# MCU_Data_collector.net
KiCad netlist of a schematic drawn in Altium Designer
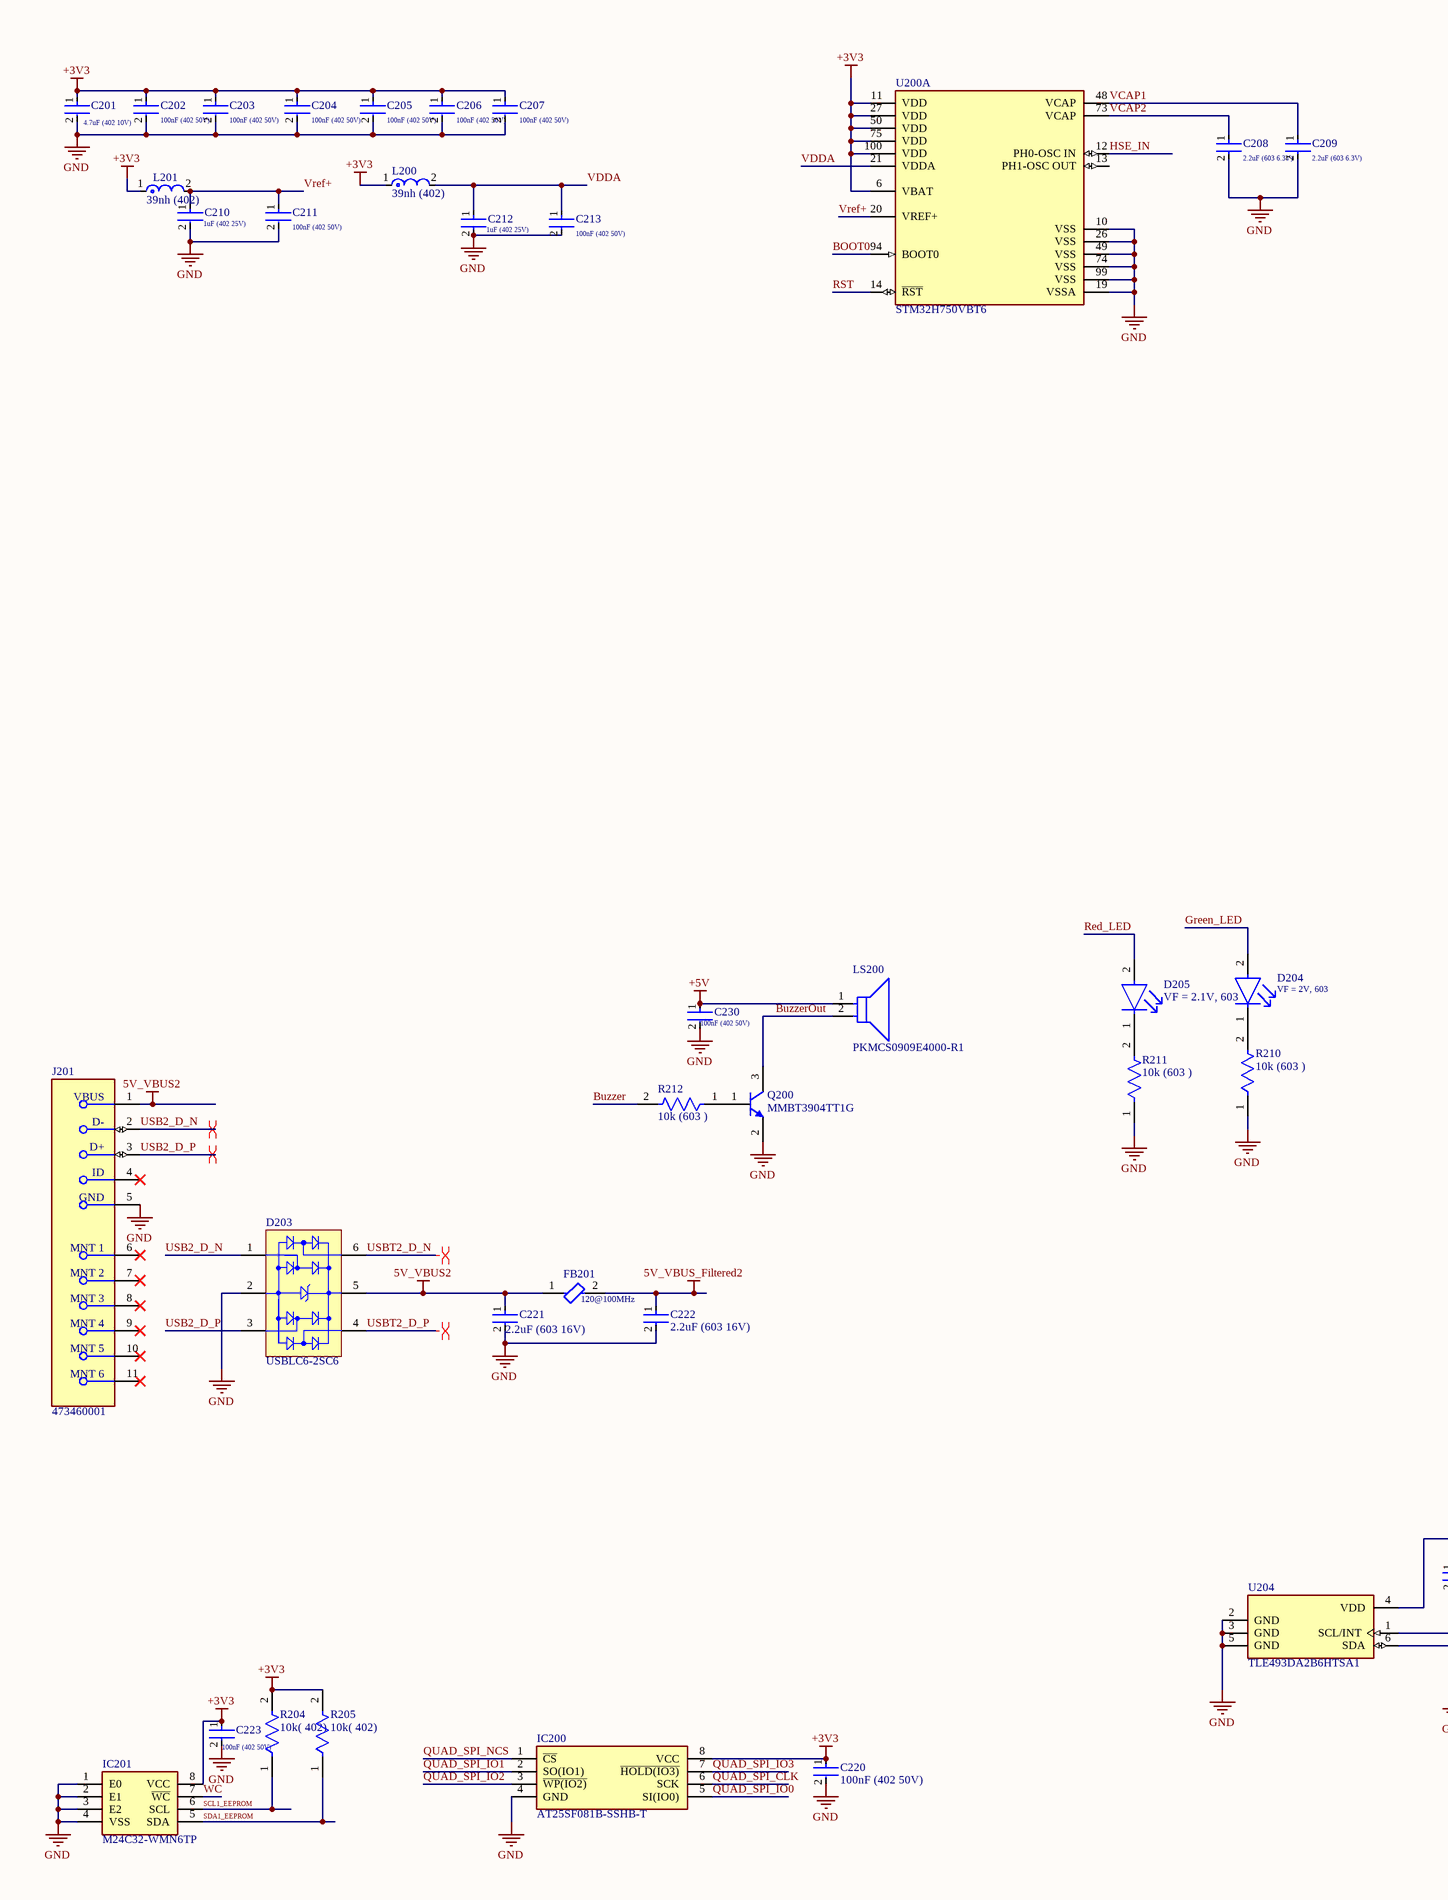
[diagram p0: MCU_Data_collector.SchDoc, left]
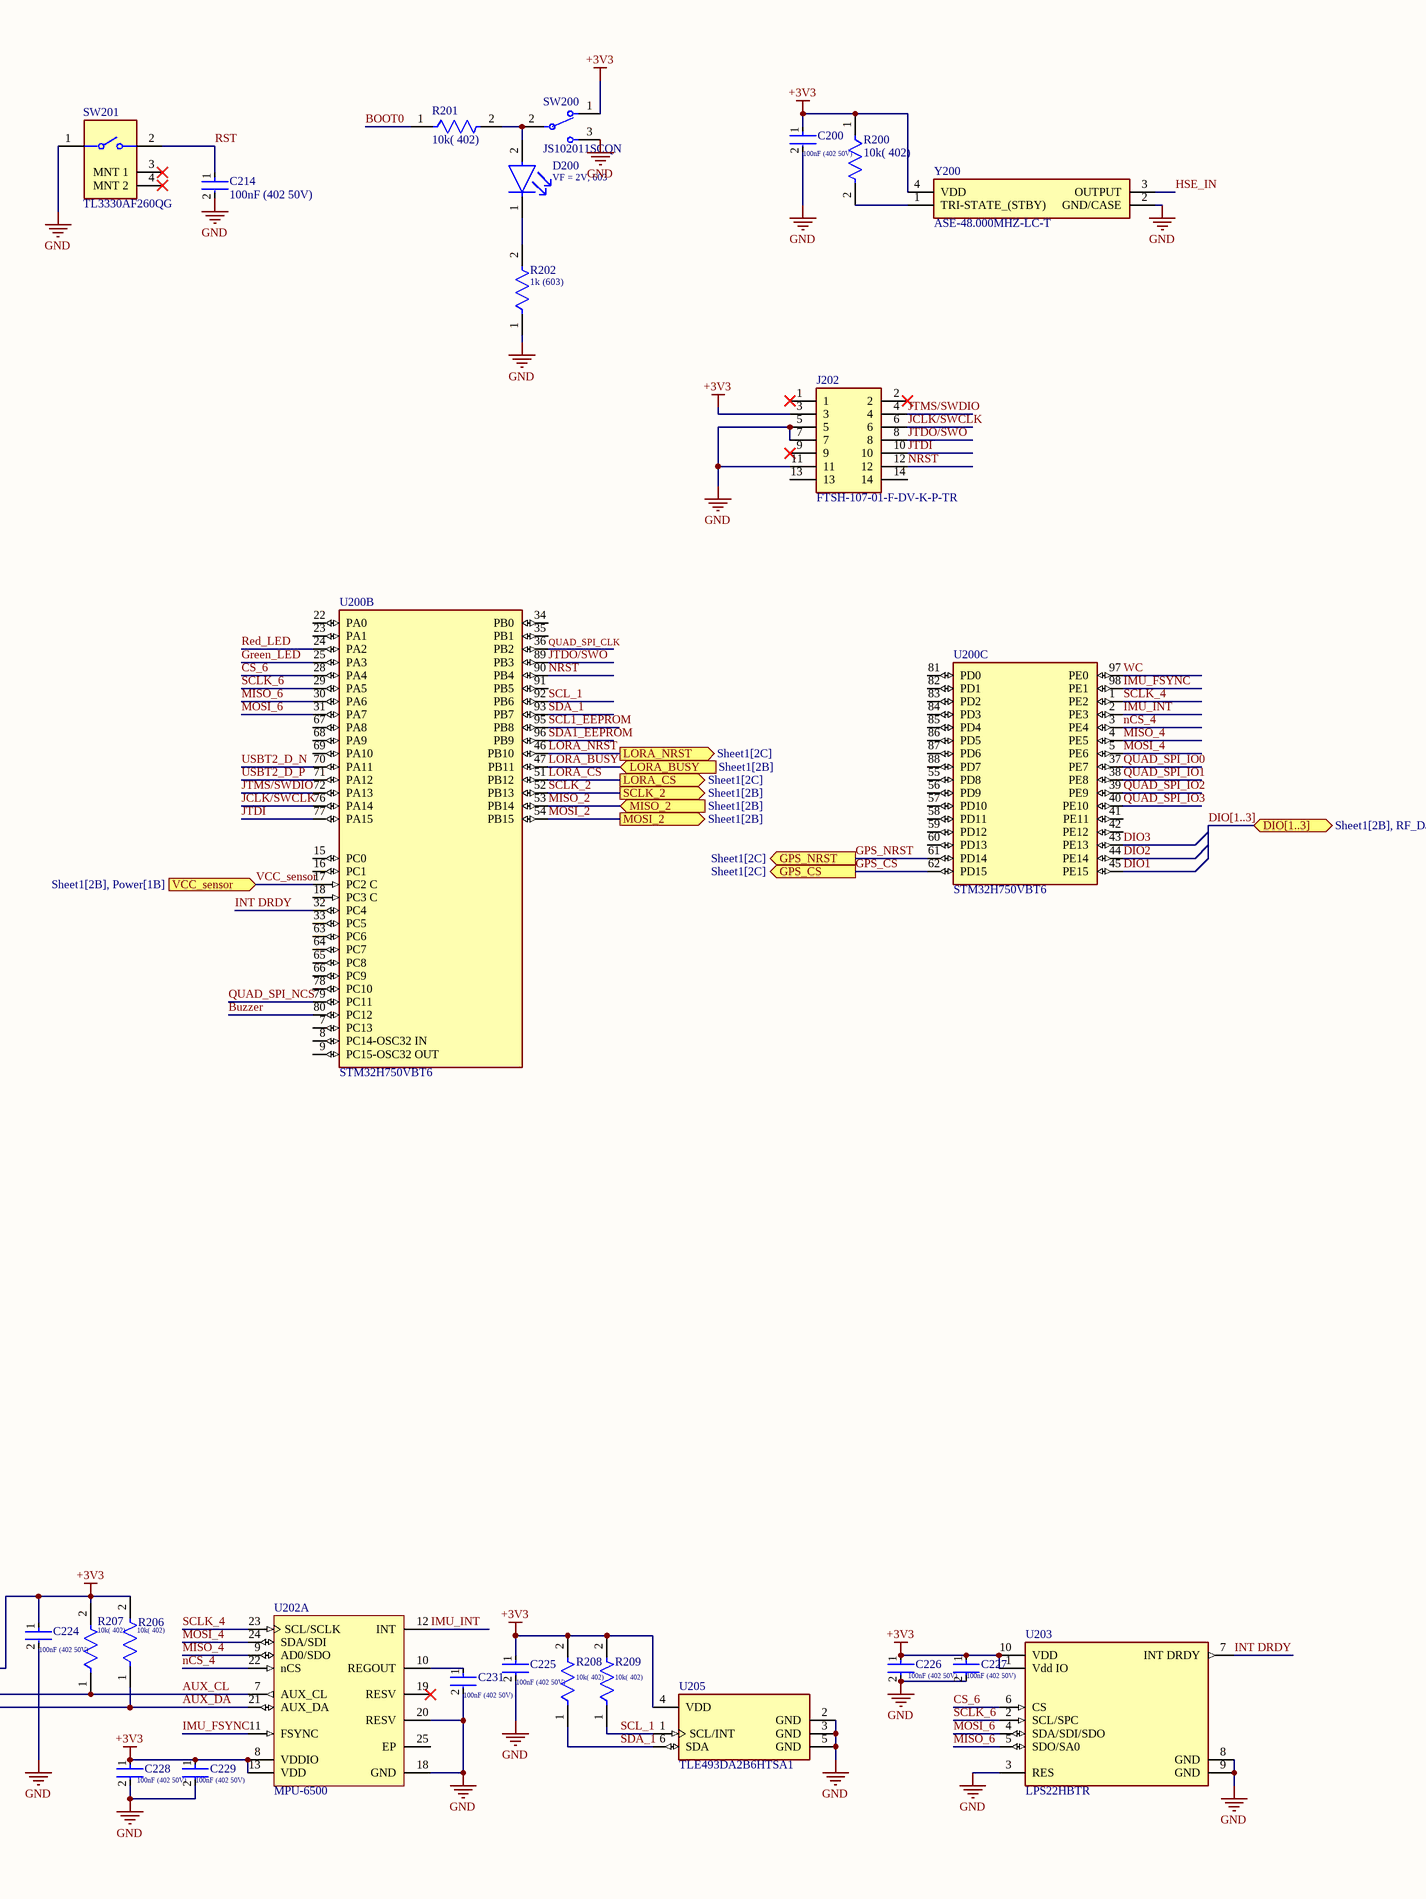
[diagram p1: MCU_Data_collector.SchDoc, right]

(export (version "E")
  (design (tool "Eeschema 10.0.6"))
  (components
    (comp (ref "C200")
      (value "100nF (402 50V)")
      (footprint "FP-CL779-IPC_C")
      (description "Cap Ceramic 100nF 50V X7R ±10% SMD 0402 +125°C Paper T/R")
      (libsource (lib "Altium Content Vault") (part "b4654b650e69147ec39a6b967a45e02"))
    )
    (comp (ref "C201")
      (value "4.7uF (402 10V)")
      (footprint "FP-CL282-IPC_C")
      (description "Cap Ceramic 4.7uF 10V X5R ±20% SMD 0402 +85°C Paper T/R")
      (fields (field (name "TOLERANCE") "20%"))
      (libsource (lib "Altium Content Vault") (part "b4654b650e69147ec39a6b967a45e02"))
    )
    (comp (ref "C202")
      (value "100nF (402 50V)")
      (footprint "FP-CL779-IPC_C")
      (description "Cap Ceramic 100nF 50V X7R ±10% SMD 0402 +125°C Paper T/R")
      (libsource (lib "Altium Content Vault") (part "b4654b650e69147ec39a6b967a45e02"))
    )
    (comp (ref "C203")
      (value "100nF (402 50V)")
      (footprint "FP-CL779-IPC_C")
      (description "Cap Ceramic 100nF 50V X7R ±10% SMD 0402 +125°C Paper T/R")
      (libsource (lib "Altium Content Vault") (part "b4654b650e69147ec39a6b967a45e02"))
    )
    (comp (ref "C204")
      (value "100nF (402 50V)")
      (footprint "FP-CL779-IPC_C")
      (description "Cap Ceramic 100nF 50V X7R ±10% SMD 0402 +125°C Paper T/R")
      (libsource (lib "Altium Content Vault") (part "b4654b650e69147ec39a6b967a45e02"))
    )
    (comp (ref "C205")
      (value "100nF (402 50V)")
      (footprint "FP-CL779-IPC_C")
      (description "Cap Ceramic 100nF 50V X7R ±10% SMD 0402 +125°C Paper T/R")
      (libsource (lib "Altium Content Vault") (part "b4654b650e69147ec39a6b967a45e02"))
    )
    (comp (ref "C206")
      (value "100nF (402 50V)")
      (footprint "FP-CL779-IPC_C")
      (description "Cap Ceramic 100nF 50V X7R ±10% SMD 0402 +125°C Paper T/R")
      (libsource (lib "Altium Content Vault") (part "b4654b650e69147ec39a6b967a45e02"))
    )
    (comp (ref "C207")
      (value "100nF (402 50V)")
      (footprint "FP-CL779-IPC_C")
      (description "Cap Ceramic 100nF 50V X7R ±10% SMD 0402 +125°C Paper T/R")
      (libsource (lib "Altium Content Vault") (part "b4654b650e69147ec39a6b967a45e02"))
    )
    (comp (ref "C208")
      (value "2.2uF (603 6.3V)")
      (footprint "FP-CL50-IPC_C")
      (description "Cap Ceramic 2.2uF 6.3V X5R ±20% SMD 0402 +85°C Paper T/R")
      (fields (field (name "TOLERANCE") "20%"))
      (libsource (lib "Altium Content Vault") (part "b4654b650e69147ec39a6b967a45e02"))
    )
    (comp (ref "C209")
      (value "2.2uF (603 6.3V)")
      (footprint "FP-CL50-IPC_C")
      (description "Cap Ceramic 2.2uF 6.3V X5R ±20% SMD 0402 +85°C Paper T/R")
      (fields (field (name "TOLERANCE") "20%"))
      (libsource (lib "Altium Content Vault") (part "b4654b650e69147ec39a6b967a45e02"))
    )
    (comp (ref "C210")
      (value "1uF (402 25V)")
      (footprint "FP-CL542-IPC_C")
      (description "Cap Ceramic 1uF 25V X5R ±10% SMD 0402 +85°C Paper T/R")
      (fields (field (name "TOLERANCE") "10%"))
      (libsource (lib "Altium Content Vault") (part "b4654b650e69147ec39a6b967a45e02"))
    )
    (comp (ref "C211")
      (value "100nF (402 50V)")
      (footprint "FP-CL779-IPC_C")
      (description "Cap Ceramic 100nF 50V X7R ±10% SMD 0402 +125°C Paper T/R")
      (libsource (lib "Altium Content Vault") (part "b4654b650e69147ec39a6b967a45e02"))
    )
    (comp (ref "C212")
      (value "1uF (402 25V)")
      (footprint "FP-CL542-IPC_C")
      (description "Cap Ceramic 1uF 25V X5R ±10% SMD 0402 +85°C Paper T/R")
      (fields (field (name "TOLERANCE") "10%"))
      (libsource (lib "Altium Content Vault") (part "b4654b650e69147ec39a6b967a45e02"))
    )
    (comp (ref "C213")
      (value "100nF (402 50V)")
      (footprint "FP-CL779-IPC_C")
      (description "Cap Ceramic 100nF 50V X7R ±10% SMD 0402 +125°C Paper T/R")
      (libsource (lib "Altium Content Vault") (part "b4654b650e69147ec39a6b967a45e02"))
    )
    (comp (ref "C214")
      (value "100nF (402 50V)")
      (footprint "FP-CL779-IPC_C")
      (description "Cap Ceramic 100nF 50V X7R ±10% SMD 0402 +125°C Paper T/R")
      (libsource (lib "Altium Content Vault") (part "b4654b650e69147ec39a6b967a45e02"))
    )
    (comp (ref "C220")
      (value "100nF (402 50V)")
      (footprint "FP-CL779-IPC_C")
      (description "Cap Ceramic 100nF 50V X7R ±10% SMD 0402 +125°C Paper T/R")
      (libsource (lib "Altium Content Vault") (part "b4654b650e69147ec39a6b967a45e02"))
    )
    (comp (ref "C221")
      (value "2.2uF (603 16V)")
      (footprint "FP-CL10-IPC_A")
      (description "Cap Ceramic 2.2uF 16V X5R ±10% Pad SMD 0603 +85°C T/R")
      (fields (field (name "TOLERANCE") "10%") (field (name "VOLTAGE") "16V"))
      (libsource (lib "Altium Content Vault") (part "b4654b650e69147ec39a6b967a45e02"))
    )
    (comp (ref "C222")
      (value "2.2uF (603 16V)")
      (footprint "FP-CL10-IPC_A")
      (description "Cap Ceramic 2.2uF 16V X5R ±10% Pad SMD 0603 +85°C T/R")
      (fields (field (name "TOLERANCE") "10%") (field (name "VOLTAGE") "16V"))
      (libsource (lib "Altium Content Vault") (part "b4654b650e69147ec39a6b967a45e02"))
    )
    (comp (ref "C223")
      (value "100nF (402 50V)")
      (footprint "FP-CL779-IPC_C")
      (description "Cap Ceramic 100nF 50V X7R ±10% SMD 0402 +125°C Paper T/R")
      (libsource (lib "Altium Content Vault") (part "b4654b650e69147ec39a6b967a45e02"))
    )
    (comp (ref "C224")
      (value "100nF (402 50V)")
      (footprint "FP-CL779-IPC_C")
      (description "Cap Ceramic 100nF 50V X7R ±10% SMD 0402 +125°C Paper T/R")
      (libsource (lib "Altium Content Vault") (part "b4654b650e69147ec39a6b967a45e02"))
    )
    (comp (ref "C225")
      (value "100nF (402 50V)")
      (footprint "FP-CL779-IPC_C")
      (description "Cap Ceramic 100nF 50V X7R ±10% SMD 0402 +125°C Paper T/R")
      (libsource (lib "Altium Content Vault") (part "b4654b650e69147ec39a6b967a45e02"))
    )
    (comp (ref "C226")
      (value "100nF (402 50V)")
      (footprint "FP-CL779-IPC_C")
      (description "Cap Ceramic 100nF 50V X7R ±10% SMD 0402 +125°C Paper T/R")
      (libsource (lib "Altium Content Vault") (part "b4654b650e69147ec39a6b967a45e02"))
    )
    (comp (ref "C227")
      (value "100nF (402 50V)")
      (footprint "FP-CL779-IPC_C")
      (description "Cap Ceramic 100nF 50V X7R ±10% SMD 0402 +125°C Paper T/R")
      (libsource (lib "Altium Content Vault") (part "b4654b650e69147ec39a6b967a45e02"))
    )
    (comp (ref "C228")
      (value "100nF (402 50V)")
      (footprint "FP-CL779-IPC_C")
      (description "Cap Ceramic 100nF 50V X7R ±10% SMD 0402 +125°C Paper T/R")
      (libsource (lib "Altium Content Vault") (part "b4654b650e69147ec39a6b967a45e02"))
    )
    (comp (ref "C229")
      (value "100nF (402 50V)")
      (footprint "FP-CL779-IPC_C")
      (description "Cap Ceramic 100nF 50V X7R ±10% SMD 0402 +125°C Paper T/R")
      (libsource (lib "Altium Content Vault") (part "b4654b650e69147ec39a6b967a45e02"))
    )
    (comp (ref "C230")
      (value "100nF (402 50V)")
      (footprint "FP-CL779-IPC_C")
      (description "Cap Ceramic 100nF 50V X7R ±10% SMD 0402 +125°C Paper T/R")
      (libsource (lib "Altium Content Vault") (part "b4654b650e69147ec39a6b967a45e02"))
    )
    (comp (ref "C231")
      (value "100nF (402 50V)")
      (footprint "FP-CL779-IPC_C")
      (description "Cap Ceramic 100nF 50V X7R ±10% SMD 0402 +125°C Paper T/R")
      (libsource (lib "Altium Content Vault") (part "b4654b650e69147ec39a6b967a45e02"))
    )
    (comp (ref "D200")
      (value "VF = 2V, 603")
      (footprint "FP-LTST-C191KGKT-MFG")
      (description "LED GREEN CLEAR SMD")
      (libsource (lib "Altium Content Vault") (part "8706943c75ba83719d021d2fdc84c58"))
    )
    (comp (ref "D203")
      (value "USBLC6-2SC6")
      (footprint "STM-SOT23-6L_V")
      (description "Very low capacitance ESD protection, 3.5 pF, -40 to 125 degC, 6-Pin SOT23, RoHS, Tape and Reel")
      (fields (field (name "MANUFACTURER") "STMicroelectronics"))
      (libsource (lib "Altium Content Vault") (part "STM-USB_DVI_HDMIULC6-4SC6X-SOT23-6L"))
    )
    (comp (ref "D204")
      (value "VF = 2V, 603")
      (footprint "FP-LTST-C191KGKT-MFG")
      (description "LED GREEN CLEAR SMD")
      (libsource (lib "Altium Content Vault") (part "8706943c75ba83719d021d2fdc84c58"))
    )
    (comp (ref "D205")
      (value "VF = 2.1V, 603")
      (footprint "FP-LTST-C190KRKT-MFG")
      (description "LED RED CLEAR CHIP SMD")
      (libsource (lib "Altium Content Vault") (part "8706943c75ba83719d021d2fdc84c58"))
    )
    (comp (ref "FB201")
      (value "120@100MHz")
      (footprint "FP-BLM18-0_15-t0_8-MFG")
      (description "Chip Ferrite Bead, 0603, 120Ω @ 100MHz, 0.25Ω, 25%, 200mA")
      (fields (field (name "TOLERANCE") "25%"))
      (libsource (lib "Altium Content Vault") (part "5f30dd21d616792df468990f7003faa"))
    )
    (comp (ref "IC200")
      (value "AT25SF081B-SSHB-T")
      (footprint "SamacSys:SOIC127P600X175-8N")
      (description "Integrated Circuit")
      (fields (field (name "MOUSER PART NUMBER") "724-AT25SF081BSSHBT"))
      (libsource (lib "*") (part "AT25SF081B-SSHB-T"))
    )
    (comp (ref "IC201")
      (value "M24C32-WMN6TP")
      (footprint "SamacSys:SOIC127P600X175-8N")
      (description "Integrated Circuit")
      (fields (field (name "MOUSER PART NUMBER") "511-M24C32-WMN6TP"))
      (libsource (lib "*") (part "M24C32-WMN6TP"))
    )
    (comp (ref "J201")
      (value "473460001")
      (footprint "FP-473460001-MFG")
      (description "CONN RCPT USB2.0 MICRO B SMD R/A")
      (fields
        (field (name "OCTOPART") "https://octopart.com/47346-0001-molex-7164928")
        (field (name "MANUFACTURER") "Molex")
      )
      (libsource (lib "Altium Content Vault") (part "53ae1f1d9b557310b43ca686e5bb76a"))
    )
    (comp (ref "J202")
      (value "FTSH-107-01-F-DV-K-P-TR")
      (footprint "SamacSys:FTSH-107-XX-YYY-DV-K-P-TR")
      (description "Connector")
      (fields (field (name "MOUSER PART NUMBER") "200-FTSH10701FDVKPTR"))
      (libsource (lib "*") (part "FTSH-107-01-F-DV-K-P-TR"))
    )
    (comp (ref "L200")
      (value "39nh (402)")
      (footprint "FP-LQG15HH_02-MFG")
      (description "Multilayer type RF Inductor 39nH ±5% 1.06Ω 250mA 0402")
      (fields (field (name "TOLERANCE") "5%"))
      (libsource (lib "Altium Content Vault") (part "4cc4b267dca4c8e51f7102f422741d8"))
    )
    (comp (ref "L201")
      (value "39nh (402)")
      (footprint "FP-LQG15HH_02-MFG")
      (description "Multilayer type RF Inductor 39nH ±5% 1.06Ω 250mA 0402")
      (fields (field (name "TOLERANCE") "5%"))
      (libsource (lib "Altium Content Vault") (part "4cc4b267dca4c8e51f7102f422741d8"))
    )
    (comp (ref "LS200")
      (value "PKMCS0909E4000-R1")
      (footprint "FP-PKMCS-MFG")
      (description "AUDIO PIEZO TRANSDUCER 12.5V SMD")
      (libsource (lib "Altium Content Vault") (part "1973c4b650225fd2ddacaff6b763965"))
    )
    (comp (ref "Q200")
      (value "MMBT3904TT1G")
      (footprint "ONSC-SC-75-3-463-01_V")
      (description "General Purpose Transistor, NPN Silicon, 3-Pin SC-75, Pb-Free, Tape and Reel")
      (fields (field (name "MANUFACTURER") "On Semiconductor"))
      (libsource (lib "Altium Content Vault") (part "ONSC-NPN-B1E2C3-3"))
    )
    (comp (ref "R200")
      (value "10k( 402)")
      (footprint "FP-RC0402-0_4-IPC_C")
      (description "RES 10K OHM 5% 1/16W 0402")
      (fields (field (name "TOLERANCE") "5%"))
      (libsource (lib "Altium Content Vault") (part "1029c3af85768c4190bb7ad29bc67b5"))
    )
    (comp (ref "R201")
      (value "10k( 402)")
      (footprint "FP-RC0402-0_4-IPC_C")
      (description "RES 10K OHM 5% 1/16W 0402")
      (fields (field (name "TOLERANCE") "5%"))
      (libsource (lib "Altium Content Vault") (part "1029c3af85768c4190bb7ad29bc67b5"))
    )
    (comp (ref "R202")
      (value "1k (603)")
      (footprint "FP-CRCW0603-e3-MFG")
      (description "RES Thick Film, 1kΩ, 1%, 0.1W, 100ppm/°C, 0603")
      (fields (field (name "TOLERANCE") "1%"))
      (libsource (lib "Altium Content Vault") (part "1029c3af85768c4190bb7ad29bc67b5"))
    )
    (comp (ref "R204")
      (value "10k( 402)")
      (footprint "FP-RC0402-0_4-IPC_C")
      (description "RES 10K OHM 5% 1/16W 0402")
      (fields (field (name "TOLERANCE") "5%"))
      (libsource (lib "Altium Content Vault") (part "1029c3af85768c4190bb7ad29bc67b5"))
    )
    (comp (ref "R205")
      (value "10k( 402)")
      (footprint "FP-RC0402-0_4-IPC_C")
      (description "RES 10K OHM 5% 1/16W 0402")
      (fields (field (name "TOLERANCE") "5%"))
      (libsource (lib "Altium Content Vault") (part "1029c3af85768c4190bb7ad29bc67b5"))
    )
    (comp (ref "R206")
      (value "10k( 402)")
      (footprint "FP-RC0402-0_4-IPC_C")
      (description "RES 10K OHM 5% 1/16W 0402")
      (fields (field (name "TOLERANCE") "5%"))
      (libsource (lib "Altium Content Vault") (part "1029c3af85768c4190bb7ad29bc67b5"))
    )
    (comp (ref "R207")
      (value "10k( 402)")
      (footprint "FP-RC0402-0_4-IPC_C")
      (description "RES 10K OHM 5% 1/16W 0402")
      (fields (field (name "TOLERANCE") "5%"))
      (libsource (lib "Altium Content Vault") (part "1029c3af85768c4190bb7ad29bc67b5"))
    )
    (comp (ref "R208")
      (value "10k( 402)")
      (footprint "FP-RC0402-0_4-IPC_C")
      (description "RES 10K OHM 5% 1/16W 0402")
      (fields (field (name "TOLERANCE") "5%"))
      (libsource (lib "Altium Content Vault") (part "1029c3af85768c4190bb7ad29bc67b5"))
    )
    (comp (ref "R209")
      (value "10k( 402)")
      (footprint "FP-RC0402-0_4-IPC_C")
      (description "RES 10K OHM 5% 1/16W 0402")
      (fields (field (name "TOLERANCE") "5%"))
      (libsource (lib "Altium Content Vault") (part "1029c3af85768c4190bb7ad29bc67b5"))
    )
    (comp (ref "R210")
      (value "10k (603 )")
      (footprint "FP-ESR03-IPC_C")
      (description "10kΩ ±5% 0.25W 0603 Anti-Surge Chip Resistor AEC-Q200")
      (fields (field (name "TOLERANCE") "5%"))
      (libsource (lib "Altium Content Vault") (part "1029c3af85768c4190bb7ad29bc67b5"))
    )
    (comp (ref "R211")
      (value "10k (603 )")
      (footprint "FP-ESR03-IPC_C")
      (description "10kΩ ±5% 0.25W 0603 Anti-Surge Chip Resistor AEC-Q200")
      (fields (field (name "TOLERANCE") "5%"))
      (libsource (lib "Altium Content Vault") (part "1029c3af85768c4190bb7ad29bc67b5"))
    )
    (comp (ref "R212")
      (value "10k (603 )")
      (footprint "FP-ESR03-IPC_C")
      (description "10kΩ ±5% 0.25W 0603 Anti-Surge Chip Resistor AEC-Q200")
      (fields (field (name "TOLERANCE") "5%"))
      (libsource (lib "Altium Content Vault") (part "1029c3af85768c4190bb7ad29bc67b5"))
    )
    (comp (ref "SW200")
      (value "JS102011SCQN")
      (footprint "FP-JS102011SCQN-MFG")
      (description "SWITCH SLIDE SPDT 300MA 6V")
      (libsource (lib "Altium Content Vault") (part "39e195cbbadc85d1df0d7eb6847d379"))
    )
    (comp (ref "SW201")
      (value "TL3330AF260QG")
      (footprint "FP-TL3330AF260QG-MFG")
      (description "SWITCH TACTILE SPST-NO 0.05A 12V")
      (libsource (lib "Altium Content Vault") (part "ba273623df615dc6639d82e10acef2d"))
    )
    (comp (ref "U200")
      (value "STM32H750VBT6")
      (footprint "FP-LQFP100-1L-MFG")
      (description "IC MCU 32BIT 128KB FLASH 100LQFP")
      (fields
        (field (name "OCTOPART") "https://octopart.com/stm32h750vbt6-stmicroelectronics-94048547")
        (field (name "MANUFACTURER") "STMicroelectronics")
      )
      (libsource (lib "Altium Content Vault") (part "aca449acb2b80670ba40d015d68dc7a"))
    )
    (comp (ref "U202")
      (value "MPU-6500")
      (footprint "INSE-MPU-6500-QFN24_M")
      (fields (field (name "MANUFACTURER") "InvenSense"))
      (libsource (lib "Altium Content Vault") (part "INSE-MPU-6500-24"))
    )
    (comp (ref "U203")
      (value "LPS22HBTR")
      (footprint "FP-HLGA-10L-8479831-0")
      (description "MEMS NANO PRESSURE SENSOR: 260-1")
      (fields
        (field (name "OCTOPART") "https://octopart.com/lps22hbtr-stmicroelectronics-51851131")
        (field (name "MANUFACTURER") "STMicroelectronics")
      )
      (libsource (lib "Altium Content Vault") (part "d4c28707ea3ba579869663dd93796c5"))
    )
    (comp (ref "U204")
      (value "TLE493DA2B6HTSA1")
      (footprint "FP-PG-TSOP6-6-MFG")
      (description "SENSOR HALL EFFECT I2C")
      (libsource (lib "Altium Content Vault") (part "e990a748e70c8c1dd7ad303904c429a"))
    )
    (comp (ref "U205")
      (value "TLE493DA2B6HTSA1")
      (footprint "FP-PG-TSOP6-6-MFG")
      (description "SENSOR HALL EFFECT I2C")
      (libsource (lib "") (part "e990a748e70c8c1dd7ad303904c429a_1"))
    )
    (comp (ref "Y200")
      (value "ASE-48.000MHZ-LC-T")
      (footprint "SamacSys:ASE24576MHZLCT")
      (description "Crystal or Oscillator")
      (fields (field (name "MOUSER PART NUMBER") "815-ASE48.000MHZLCT"))
      (libsource (lib "*") (part "ASE-48.000MHZ-LC-T"))
    )
  )
  (nets
    (net (code "1") (name "+3V3") (class "Default")
      (node (ref "C200") (pin "1") (pinfunction "1_1") (pintype "passive"))
      (node (ref "C201") (pin "1") (pinfunction "1_1") (pintype "passive"))
      (node (ref "C202") (pin "1") (pinfunction "1_1") (pintype "passive"))
      (node (ref "C203") (pin "1") (pinfunction "1_1") (pintype "passive"))
      (node (ref "C204") (pin "1") (pinfunction "1_1") (pintype "passive"))
      (node (ref "C205") (pin "1") (pinfunction "1_1") (pintype "passive"))
      (node (ref "C206") (pin "1") (pinfunction "1_1") (pintype "passive"))
      (node (ref "C207") (pin "1") (pinfunction "1_1") (pintype "passive"))
      (node (ref "C220") (pin "1") (pinfunction "1_1") (pintype "passive"))
      (node (ref "C223") (pin "1") (pinfunction "1_1") (pintype "passive"))
      (node (ref "C224") (pin "1") (pinfunction "1_1") (pintype "passive"))
      (node (ref "C225") (pin "1") (pinfunction "1_1") (pintype "passive"))
      (node (ref "C226") (pin "1") (pinfunction "1_1") (pintype "passive"))
      (node (ref "C227") (pin "1") (pinfunction "1_1") (pintype "passive"))
      (node (ref "C228") (pin "1") (pinfunction "1_1") (pintype "passive"))
      (node (ref "C229") (pin "1") (pinfunction "1_1") (pintype "passive"))
      (node (ref "IC200") (pin "8") (pinfunction "VCC_8") (pintype "passive"))
      (node (ref "IC201") (pin "8") (pinfunction "VCC_8") (pintype "passive"))
      (node (ref "J202") (pin "3") (pinfunction "3_3") (pintype "passive"))
      (node (ref "L200") (pin "1") (pinfunction "1_1") (pintype "passive"))
      (node (ref "L201") (pin "1") (pinfunction "1_1") (pintype "passive"))
      (node (ref "R200") (pin "1") (pinfunction "1_1") (pintype "passive"))
      (node (ref "R204") (pin "2") (pinfunction "2_2") (pintype "passive"))
      (node (ref "R205") (pin "2") (pinfunction "2_2") (pintype "passive"))
      (node (ref "R206") (pin "2") (pinfunction "2_2") (pintype "passive"))
      (node (ref "R207") (pin "2") (pinfunction "2_2") (pintype "passive"))
      (node (ref "R208") (pin "2") (pinfunction "2_2") (pintype "passive"))
      (node (ref "R209") (pin "2") (pinfunction "2_2") (pintype "passive"))
      (node (ref "SW200") (pin "1") (pinfunction "1_1") (pintype "passive"))
      (node (ref "U200") (pin "100") (pinfunction "VDD_100") (pintype "power_in"))
      (node (ref "U200") (pin "11") (pinfunction "VDD_11") (pintype "power_in"))
      (node (ref "U200") (pin "27") (pinfunction "VDD_27") (pintype "power_in"))
      (node (ref "U200") (pin "50") (pinfunction "VDD_50") (pintype "power_in"))
      (node (ref "U200") (pin "6") (pinfunction "VBAT_6") (pintype "power_in"))
      (node (ref "U200") (pin "75") (pinfunction "VDD_75") (pintype "power_in"))
      (node (ref "U202") (pin "13") (pinfunction "VDD_13") (pintype "power_in"))
      (node (ref "U202") (pin "8") (pinfunction "VDDIO_8") (pintype "power_in"))
      (node (ref "U203") (pin "1") (pinfunction "Vdd_IO_1") (pintype "power_in"))
      (node (ref "U203") (pin "10") (pinfunction "VDD_10") (pintype "power_in"))
      (node (ref "U204") (pin "4") (pinfunction "VDD_4") (pintype "power_in"))
      (node (ref "U205") (pin "4") (pinfunction "VDD_4") (pintype "power_in"))
      (node (ref "Y200") (pin "4") (pinfunction "VDD_4") (pintype "passive"))
    )
    (net (code "2") (name "+5V") (class "Default")
      (node (ref "C230") (pin "1") (pinfunction "1_1") (pintype "passive"))
      (node (ref "LS200") (pin "1") (pinfunction "C_1") (pintype "passive"))
    )
    (net (code "3") (name "/AUX_CL") (class "Default")
      (node (ref "R207") (pin "1") (pinfunction "1_1") (pintype "passive"))
      (node (ref "U202") (pin "7") (pinfunction "AUX_CL_7") (pintype "output"))
      (node (ref "U204") (pin "1") (pinfunction "SCL/INT_1") (pintype "input"))
    )
    (net (code "4") (name "/AUX_DA") (class "Default")
      (node (ref "R206") (pin "1") (pinfunction "1_1") (pintype "passive"))
      (node (ref "U202") (pin "21") (pinfunction "AUX_DA_21") (pintype "bidirectional"))
      (node (ref "U204") (pin "6") (pinfunction "SDA_6") (pintype "bidirectional"))
    )
    (net (code "5") (name "/BOOT0") (class "Default")
      (node (ref "R201") (pin "1") (pinfunction "1_1") (pintype "passive"))
      (node (ref "U200") (pin "94") (pinfunction "BOOT0_94") (pintype "input"))
    )
    (net (code "6") (name "/Buzzer") (class "Default")
      (node (ref "R212") (pin "2") (pinfunction "2_2") (pintype "passive"))
      (node (ref "U200") (pin "80") (pinfunction "PC12_80") (pintype "bidirectional"))
    )
    (net (code "7") (name "/BuzzerOut") (class "Default")
      (node (ref "LS200") (pin "2") (pinfunction "A_2") (pintype "passive"))
      (node (ref "Q200") (pin "3") (pinfunction "C_3") (pintype "passive"))
    )
    (net (code "8") (name "/CS_6") (class "Default")
      (node (ref "U200") (pin "28") (pinfunction "PA4_28") (pintype "bidirectional"))
      (node (ref "U203") (pin "6") (pinfunction "CS_6") (pintype "input"))
    )
    (net (code "9") (name "/DIO1") (class "Default")
      (node (ref "U200") (pin "45") (pinfunction "PE15_45") (pintype "bidirectional"))
    )
    (net (code "10") (name "/DIO2") (class "Default")
      (node (ref "U200") (pin "44") (pinfunction "PE14_44") (pintype "bidirectional"))
    )
    (net (code "11") (name "/DIO3") (class "Default")
      (node (ref "U200") (pin "43") (pinfunction "PE13_43") (pintype "bidirectional"))
    )
    (net (code "13") (name "/GPS_CS") (class "Default")
      (node (ref "U200") (pin "62") (pinfunction "PD15_62") (pintype "bidirectional"))
    )
    (net (code "14") (name "/GPS_NRST") (class "Default")
      (node (ref "U200") (pin "61") (pinfunction "PD14_61") (pintype "bidirectional"))
    )
    (net (code "15") (name "/Green_LED") (class "Default")
      (node (ref "D204") (pin "2") (pinfunction "A_2") (pintype "passive"))
      (node (ref "U200") (pin "25") (pinfunction "PA3_25") (pintype "bidirectional"))
    )
    (net (code "16") (name "/HSE_IN") (class "Default")
      (node (ref "U200") (pin "12") (pinfunction "PH0-OSC_IN_12") (pintype "bidirectional"))
      (node (ref "Y200") (pin "3") (pinfunction "OUTPUT_3") (pintype "passive"))
    )
    (net (code "17") (name "/IMU_FSYNC") (class "Default")
      (node (ref "U200") (pin "98") (pinfunction "PE1_98") (pintype "bidirectional"))
      (node (ref "U202") (pin "11") (pinfunction "FSYNC_11") (pintype "input"))
    )
    (net (code "18") (name "/IMU_INT") (class "Default")
      (node (ref "U200") (pin "2") (pinfunction "PE3_2") (pintype "bidirectional"))
      (node (ref "U202") (pin "12") (pinfunction "INT_12") (pintype "open_collector"))
    )
    (net (code "19") (name "/INT DRDY") (class "Default")
      (node (ref "U200") (pin "32") (pinfunction "PC4_32") (pintype "bidirectional"))
      (node (ref "U203") (pin "7") (pinfunction "INT_DRDY_7") (pintype "output"))
    )
    (net (code "20") (name "/JCLK{slash}SWCLK") (class "Default")
      (node (ref "J202") (pin "6") (pinfunction "6_6") (pintype "passive"))
      (node (ref "U200") (pin "76") (pinfunction "PA14_76") (pintype "bidirectional"))
    )
    (net (code "21") (name "/JTDI") (class "Default")
      (node (ref "J202") (pin "10") (pinfunction "10_10") (pintype "passive"))
      (node (ref "U200") (pin "77") (pinfunction "PA15_77") (pintype "bidirectional"))
    )
    (net (code "22") (name "/JTDO{slash}SWO") (class "Default")
      (node (ref "J202") (pin "8") (pinfunction "8_8") (pintype "passive"))
      (node (ref "U200") (pin "89") (pinfunction "PB3_89") (pintype "bidirectional"))
    )
    (net (code "23") (name "/JTMS{slash}SWDIO") (class "Default")
      (node (ref "J202") (pin "4") (pinfunction "4_4") (pintype "passive"))
      (node (ref "U200") (pin "72") (pinfunction "PA13_72") (pintype "bidirectional"))
    )
    (net (code "24") (name "/LORA_BUSY") (class "Default")
      (node (ref "U200") (pin "47") (pinfunction "PB11_47") (pintype "bidirectional"))
    )
    (net (code "25") (name "/LORA_CS") (class "Default")
      (node (ref "U200") (pin "51") (pinfunction "PB12_51") (pintype "bidirectional"))
    )
    (net (code "26") (name "/LORA_NRST") (class "Default")
      (node (ref "U200") (pin "46") (pinfunction "PB10_46") (pintype "bidirectional"))
    )
    (net (code "27") (name "/MISO_2") (class "Default")
      (node (ref "U200") (pin "53") (pinfunction "PB14_53") (pintype "bidirectional"))
    )
    (net (code "28") (name "/MISO_4") (class "Default")
      (node (ref "U200") (pin "4") (pinfunction "PE5_4") (pintype "bidirectional"))
      (node (ref "U202") (pin "9") (pinfunction "AD0/SDO_9") (pintype "bidirectional"))
    )
    (net (code "29") (name "/MISO_6") (class "Default")
      (node (ref "U200") (pin "30") (pinfunction "PA6_30") (pintype "bidirectional"))
      (node (ref "U203") (pin "5") (pinfunction "SDO/SA0_5") (pintype "bidirectional"))
    )
    (net (code "30") (name "/MOSI_2") (class "Default")
      (node (ref "U200") (pin "54") (pinfunction "PB15_54") (pintype "bidirectional"))
    )
    (net (code "31") (name "/MOSI_4") (class "Default")
      (node (ref "U200") (pin "5") (pinfunction "PE6_5") (pintype "bidirectional"))
      (node (ref "U202") (pin "24") (pinfunction "SDA/SDI_24") (pintype "bidirectional"))
    )
    (net (code "32") (name "/MOSI_6") (class "Default")
      (node (ref "U200") (pin "31") (pinfunction "PA7_31") (pintype "bidirectional"))
      (node (ref "U203") (pin "4") (pinfunction "SDA/SDI/SDO_4") (pintype "bidirectional"))
    )
    (net (code "33") (name "/NRST") (class "Default")
      (node (ref "J202") (pin "12") (pinfunction "12_12") (pintype "passive"))
      (node (ref "U200") (pin "90") (pinfunction "PB4_90") (pintype "bidirectional"))
    )
    (net (code "34") (name "/QUAD_SPI_CLK") (class "Default")
      (node (ref "IC200") (pin "6") (pinfunction "SCK_6") (pintype "passive"))
      (node (ref "U200") (pin "36") (pinfunction "PB2_36") (pintype "bidirectional"))
    )
    (net (code "35") (name "/QUAD_SPI_IO0") (class "Default")
      (node (ref "IC200") (pin "5") (pinfunction "SI(IO0)_5") (pintype "passive"))
      (node (ref "U200") (pin "37") (pinfunction "PE7_37") (pintype "bidirectional"))
    )
    (net (code "36") (name "/QUAD_SPI_IO1") (class "Default")
      (node (ref "IC200") (pin "2") (pinfunction "SO(IO1)_2") (pintype "passive"))
      (node (ref "U200") (pin "38") (pinfunction "PE8_38") (pintype "bidirectional"))
    )
    (net (code "37") (name "/QUAD_SPI_IO2") (class "Default")
      (node (ref "IC200") (pin "3") (pinfunction "~{WP(IO2)}_3") (pintype "passive"))
      (node (ref "U200") (pin "39") (pinfunction "PE9_39") (pintype "bidirectional"))
    )
    (net (code "38") (name "/QUAD_SPI_IO3") (class "Default")
      (node (ref "IC200") (pin "7") (pinfunction "~{HOLD(IO3)}_7") (pintype "passive"))
      (node (ref "U200") (pin "40") (pinfunction "PE10_40") (pintype "bidirectional"))
    )
    (net (code "39") (name "/QUAD_SPI_NCS") (class "Default")
      (node (ref "IC200") (pin "1") (pinfunction "~{CS}_1") (pintype "passive"))
      (node (ref "U200") (pin "79") (pinfunction "PC11_79") (pintype "bidirectional"))
    )
    (net (code "40") (name "/RST") (class "Default")
      (node (ref "C214") (pin "1") (pinfunction "1_1") (pintype "passive"))
      (node (ref "SW201") (pin "2") (pinfunction "2_2") (pintype "passive"))
      (node (ref "U200") (pin "14") (pinfunction "~{RST}_14") (pintype "bidirectional"))
    )
    (net (code "41") (name "/Red_LED") (class "Default")
      (node (ref "D205") (pin "2") (pinfunction "A_2") (pintype "passive"))
      (node (ref "U200") (pin "24") (pinfunction "PA2_24") (pintype "bidirectional"))
    )
    (net (code "42") (name "/SCL1_EEPROM") (class "Default")
      (node (ref "IC201") (pin "6") (pinfunction "SCL_6") (pintype "passive"))
      (node (ref "R204") (pin "1") (pinfunction "1_1") (pintype "passive"))
      (node (ref "U200") (pin "95") (pinfunction "PB8_95") (pintype "bidirectional"))
    )
    (net (code "43") (name "/SCLK_2") (class "Default")
      (node (ref "U200") (pin "52") (pinfunction "PB13_52") (pintype "bidirectional"))
    )
    (net (code "44") (name "/SCLK_4") (class "Default")
      (node (ref "U200") (pin "1") (pinfunction "PE2_1") (pintype "bidirectional"))
      (node (ref "U202") (pin "23") (pinfunction "SCL/SCLK_23") (pintype "input"))
    )
    (net (code "45") (name "/SCLK_6") (class "Default")
      (node (ref "U200") (pin "29") (pinfunction "PA5_29") (pintype "bidirectional"))
      (node (ref "U203") (pin "2") (pinfunction "SCL/SPC_2") (pintype "input"))
    )
    (net (code "46") (name "/SCL_1") (class "Default")
      (node (ref "R209") (pin "1") (pinfunction "1_1") (pintype "passive"))
      (node (ref "U200") (pin "92") (pinfunction "PB6_92") (pintype "bidirectional"))
      (node (ref "U205") (pin "1") (pinfunction "SCL/INT_1") (pintype "input"))
    )
    (net (code "47") (name "/SDA1_EEPROM") (class "Default")
      (node (ref "IC201") (pin "5") (pinfunction "SDA_5") (pintype "passive"))
      (node (ref "R205") (pin "1") (pinfunction "1_1") (pintype "passive"))
      (node (ref "U200") (pin "96") (pinfunction "PB9_96") (pintype "bidirectional"))
    )
    (net (code "48") (name "/SDA_1") (class "Default")
      (node (ref "R208") (pin "1") (pinfunction "1_1") (pintype "passive"))
      (node (ref "U200") (pin "93") (pinfunction "PB7_93") (pintype "bidirectional"))
      (node (ref "U205") (pin "6") (pinfunction "SDA_6") (pintype "bidirectional"))
    )
    (net (code "49") (name "/USB2_D_N") (class "Default")
      (node (ref "D203") (pin "1") (pinfunction "I/O_1_1") (pintype "passive"))
      (node (ref "J201") (pin "2") (pinfunction "D-_2") (pintype "bidirectional"))
    )
    (net (code "50") (name "/USB2_D_P") (class "Default")
      (node (ref "D203") (pin "3") (pinfunction "I/O_2_3") (pintype "passive"))
      (node (ref "J201") (pin "3") (pinfunction "D+_3") (pintype "bidirectional"))
    )
    (net (code "51") (name "/USBT2_D_N") (class "Default")
      (node (ref "D203") (pin "6") (pinfunction "I/O_4_6") (pintype "passive"))
      (node (ref "U200") (pin "70") (pinfunction "PA11_70") (pintype "bidirectional"))
    )
    (net (code "52") (name "/USBT2_D_P") (class "Default")
      (node (ref "D203") (pin "4") (pinfunction "I/O_3_4") (pintype "passive"))
      (node (ref "U200") (pin "71") (pinfunction "PA12_71") (pintype "bidirectional"))
    )
    (net (code "53") (name "/VCAP1") (class "Default")
      (node (ref "C209") (pin "1") (pinfunction "1_1") (pintype "passive"))
      (node (ref "U200") (pin "48") (pinfunction "VCAP_48") (pintype "power_in"))
    )
    (net (code "54") (name "/VCAP2") (class "Default")
      (node (ref "C208") (pin "1") (pinfunction "1_1") (pintype "passive"))
      (node (ref "U200") (pin "73") (pinfunction "VCAP_73") (pintype "power_in"))
    )
    (net (code "55") (name "/VCC_sensor") (class "Default")
      (node (ref "U200") (pin "17") (pinfunction "PC2_C_17") (pintype "input"))
    )
    (net (code "56") (name "/VDDA") (class "Default")
      (node (ref "C212") (pin "1") (pinfunction "1_1") (pintype "passive"))
      (node (ref "C213") (pin "1") (pinfunction "1_1") (pintype "passive"))
      (node (ref "L200") (pin "2") (pinfunction "2_2") (pintype "passive"))
      (node (ref "U200") (pin "21") (pinfunction "VDDA_21") (pintype "power_in"))
    )
    (net (code "57") (name "/Vref+") (class "Default")
      (node (ref "C210") (pin "1") (pinfunction "1_1") (pintype "passive"))
      (node (ref "C211") (pin "1") (pinfunction "1_1") (pintype "passive"))
      (node (ref "L201") (pin "2") (pinfunction "2_2") (pintype "passive"))
      (node (ref "U200") (pin "20") (pinfunction "VREF+_20") (pintype "power_in"))
    )
    (net (code "58") (name "/WC") (class "Default")
      (node (ref "IC201") (pin "7") (pinfunction "~{WC}_7") (pintype "passive"))
      (node (ref "U200") (pin "97") (pinfunction "PE0_97") (pintype "bidirectional"))
    )
    (net (code "59") (name "/nCS_4") (class "Default")
      (node (ref "U200") (pin "3") (pinfunction "PE4_3") (pintype "bidirectional"))
      (node (ref "U202") (pin "22") (pinfunction "nCS_22") (pintype "input"))
    )
    (net (code "60") (name "5V_VBUS2") (class "Default")
      (node (ref "C221") (pin "1") (pinfunction "1_1") (pintype "passive"))
      (node (ref "D203") (pin "5") (pinfunction "VBUS_5") (pintype "passive"))
      (node (ref "FB201") (pin "1") (pinfunction "1_1") (pintype "passive"))
      (node (ref "J201") (pin "1") (pinfunction "VBUS_1") (pintype "power_in"))
    )
    (net (code "61") (name "5V_VBUS_Filtered2") (class "Default")
      (node (ref "C222") (pin "1") (pinfunction "1_1") (pintype "passive"))
      (node (ref "FB201") (pin "2") (pinfunction "2_2") (pintype "passive"))
    )
    (net (code "62") (name "GND") (class "Default")
      (node (ref "C200") (pin "2") (pinfunction "2_2") (pintype "passive"))
      (node (ref "C201") (pin "2") (pinfunction "2_2") (pintype "passive"))
      (node (ref "C202") (pin "2") (pinfunction "2_2") (pintype "passive"))
      (node (ref "C203") (pin "2") (pinfunction "2_2") (pintype "passive"))
      (node (ref "C204") (pin "2") (pinfunction "2_2") (pintype "passive"))
      (node (ref "C205") (pin "2") (pinfunction "2_2") (pintype "passive"))
      (node (ref "C206") (pin "2") (pinfunction "2_2") (pintype "passive"))
      (node (ref "C207") (pin "2") (pinfunction "2_2") (pintype "passive"))
      (node (ref "C208") (pin "2") (pinfunction "2_2") (pintype "passive"))
      (node (ref "C209") (pin "2") (pinfunction "2_2") (pintype "passive"))
      (node (ref "C210") (pin "2") (pinfunction "2_2") (pintype "passive"))
      (node (ref "C211") (pin "2") (pinfunction "2_2") (pintype "passive"))
      (node (ref "C212") (pin "2") (pinfunction "2_2") (pintype "passive"))
      (node (ref "C213") (pin "2") (pinfunction "2_2") (pintype "passive"))
      (node (ref "C214") (pin "2") (pinfunction "2_2") (pintype "passive"))
      (node (ref "C220") (pin "2") (pinfunction "2_2") (pintype "passive"))
      (node (ref "C221") (pin "2") (pinfunction "2_2") (pintype "passive"))
      (node (ref "C222") (pin "2") (pinfunction "2_2") (pintype "passive"))
      (node (ref "C223") (pin "2") (pinfunction "2_2") (pintype "passive"))
      (node (ref "C224") (pin "2") (pinfunction "2_2") (pintype "passive"))
      (node (ref "C225") (pin "2") (pinfunction "2_2") (pintype "passive"))
      (node (ref "C226") (pin "2") (pinfunction "2_2") (pintype "passive"))
      (node (ref "C227") (pin "2") (pinfunction "2_2") (pintype "passive"))
      (node (ref "C228") (pin "2") (pinfunction "2_2") (pintype "passive"))
      (node (ref "C229") (pin "2") (pinfunction "2_2") (pintype "passive"))
      (node (ref "C230") (pin "2") (pinfunction "2_2") (pintype "passive"))
      (node (ref "C231") (pin "2") (pinfunction "2_2") (pintype "passive"))
      (node (ref "D203") (pin "2") (pinfunction "GND_2") (pintype "passive"))
      (node (ref "IC200") (pin "4") (pinfunction "GND_4") (pintype "passive"))
      (node (ref "IC201") (pin "1") (pinfunction "E0_1") (pintype "passive"))
      (node (ref "IC201") (pin "2") (pinfunction "E1_2") (pintype "passive"))
      (node (ref "IC201") (pin "3") (pinfunction "E2_3") (pintype "passive"))
      (node (ref "IC201") (pin "4") (pinfunction "VSS_4") (pintype "passive"))
      (node (ref "J201") (pin "5") (pinfunction "GND_5") (pintype "power_in"))
      (node (ref "J202") (pin "11") (pinfunction "11_11") (pintype "passive"))
      (node (ref "J202") (pin "5") (pinfunction "5_5") (pintype "passive"))
      (node (ref "J202") (pin "7") (pinfunction "7_7") (pintype "passive"))
      (node (ref "Q200") (pin "2") (pinfunction "E_2") (pintype "passive"))
      (node (ref "R202") (pin "1") (pinfunction "1_1") (pintype "passive"))
      (node (ref "R210") (pin "1") (pinfunction "1_1") (pintype "passive"))
      (node (ref "R211") (pin "1") (pinfunction "1_1") (pintype "passive"))
      (node (ref "SW200") (pin "3") (pinfunction "3_3") (pintype "passive"))
      (node (ref "SW201") (pin "1") (pinfunction "1_1") (pintype "passive"))
      (node (ref "U200") (pin "10") (pinfunction "VSS_10") (pintype "power_in"))
      (node (ref "U200") (pin "19") (pinfunction "VSSA_19") (pintype "power_in"))
      (node (ref "U200") (pin "26") (pinfunction "VSS_26") (pintype "power_in"))
      (node (ref "U200") (pin "49") (pinfunction "VSS_49") (pintype "power_in"))
      (node (ref "U200") (pin "74") (pinfunction "VSS_74") (pintype "power_in"))
      (node (ref "U200") (pin "99") (pinfunction "VSS_99") (pintype "power_in"))
      (node (ref "U202") (pin "18") (pinfunction "GND_18") (pintype "power_in"))
      (node (ref "U202") (pin "20") (pinfunction "RESV_20") (pintype "power_in"))
      (node (ref "U203") (pin "3") (pinfunction "RES_3") (pintype "passive"))
      (node (ref "U203") (pin "8") (pinfunction "GND_8") (pintype "power_in"))
      (node (ref "U203") (pin "9") (pinfunction "GND_9") (pintype "power_in"))
      (node (ref "U204") (pin "2") (pinfunction "GND_2") (pintype "power_in"))
      (node (ref "U204") (pin "3") (pinfunction "GND_3") (pintype "power_in"))
      (node (ref "U204") (pin "5") (pinfunction "GND_5") (pintype "power_in"))
      (node (ref "U205") (pin "2") (pinfunction "GND_2") (pintype "power_in"))
      (node (ref "U205") (pin "3") (pinfunction "GND_3") (pintype "power_in"))
      (node (ref "U205") (pin "5") (pinfunction "GND_5") (pintype "power_in"))
      (node (ref "Y200") (pin "2") (pinfunction "GND/CASE_2") (pintype "passive"))
    )
    (net (code "63") (name "Net-(D200-A)") (class "Default")
      (node (ref "D200") (pin "2") (pinfunction "A_2") (pintype "passive"))
      (node (ref "R201") (pin "2") (pinfunction "2_2") (pintype "passive"))
      (node (ref "SW200") (pin "2") (pinfunction "C_2") (pintype "passive"))
    )
    (net (code "64") (name "Net-(D200-C)") (class "Default")
      (node (ref "D200") (pin "1") (pinfunction "C_1") (pintype "passive"))
      (node (ref "R202") (pin "2") (pinfunction "2_2") (pintype "passive"))
    )
    (net (code "65") (name "Net-(D204-C)") (class "Default")
      (node (ref "D204") (pin "1") (pinfunction "C_1") (pintype "passive"))
      (node (ref "R210") (pin "2") (pinfunction "2_2") (pintype "passive"))
    )
    (net (code "66") (name "Net-(D205-C)") (class "Default")
      (node (ref "D205") (pin "1") (pinfunction "C_1") (pintype "passive"))
      (node (ref "R211") (pin "2") (pinfunction "2_2") (pintype "passive"))
    )
    (net (code "67") (name "Net-(Q200-B)") (class "Default")
      (node (ref "Q200") (pin "1") (pinfunction "B_1") (pintype "passive"))
      (node (ref "R212") (pin "1") (pinfunction "1_1") (pintype "passive"))
    )
    (net (code "68") (name "Net-(U202A-REGOUT)") (class "Default")
      (node (ref "C231") (pin "1") (pinfunction "1_1") (pintype "passive"))
      (node (ref "U202") (pin "10") (pinfunction "REGOUT_10") (pintype "passive"))
    )
    (net (code "69") (name "Net-(Y200-TRI-STATE_(STBY))") (class "Default")
      (node (ref "R200") (pin "2") (pinfunction "2_2") (pintype "passive"))
      (node (ref "Y200") (pin "1") (pinfunction "TRI-STATE_(STBY)_1") (pintype "passive"))
    )
    (net (code "70") (name "unconnected-(J201-ID-Pad4)") (class "Default")
      (node (ref "J201") (pin "4") (pinfunction "ID_4") (pintype "passive+no_connect"))
    )
    (net (code "71") (name "unconnected-(J201-MNT_1-Pad6)") (class "Default")
      (node (ref "J201") (pin "6") (pinfunction "MNT_1_6") (pintype "passive+no_connect"))
    )
    (net (code "72") (name "unconnected-(J201-MNT_2-Pad7)") (class "Default")
      (node (ref "J201") (pin "7") (pinfunction "MNT_2_7") (pintype "passive+no_connect"))
    )
    (net (code "73") (name "unconnected-(J201-MNT_3-Pad8)") (class "Default")
      (node (ref "J201") (pin "8") (pinfunction "MNT_3_8") (pintype "passive+no_connect"))
    )
    (net (code "74") (name "unconnected-(J201-MNT_4-Pad9)") (class "Default")
      (node (ref "J201") (pin "9") (pinfunction "MNT_4_9") (pintype "passive+no_connect"))
    )
    (net (code "75") (name "unconnected-(J201-MNT_5-Pad10)") (class "Default")
      (node (ref "J201") (pin "10") (pinfunction "MNT_5_10") (pintype "passive+no_connect"))
    )
    (net (code "76") (name "unconnected-(J201-MNT_6-Pad11)") (class "Default")
      (node (ref "J201") (pin "11") (pinfunction "MNT_6_11") (pintype "passive+no_connect"))
    )
    (net (code "77") (name "unconnected-(J202-Pad1)") (class "Default")
      (node (ref "J202") (pin "1") (pinfunction "1_1") (pintype "passive+no_connect"))
    )
    (net (code "78") (name "unconnected-(J202-Pad2)") (class "Default")
      (node (ref "J202") (pin "2") (pinfunction "2_2") (pintype "passive+no_connect"))
    )
    (net (code "79") (name "unconnected-(J202-Pad9)") (class "Default")
      (node (ref "J202") (pin "9") (pinfunction "9_9") (pintype "passive+no_connect"))
    )
    (net (code "80") (name "unconnected-(J202-Pad13)") (class "Default")
      (node (ref "J202") (pin "13") (pinfunction "13_13") (pintype "passive"))
    )
    (net (code "81") (name "unconnected-(J202-Pad14)") (class "Default")
      (node (ref "J202") (pin "14") (pinfunction "14_14") (pintype "passive"))
    )
    (net (code "82") (name "unconnected-(SW201-MNT_1-Pad3)") (class "Default")
      (node (ref "SW201") (pin "3") (pinfunction "MNT_1_3") (pintype "passive+no_connect"))
    )
    (net (code "83") (name "unconnected-(SW201-MNT_2-Pad4)") (class "Default")
      (node (ref "SW201") (pin "4") (pinfunction "MNT_2_4") (pintype "passive+no_connect"))
    )
    (net (code "84") (name "unconnected-(U200A-PH1-OSC_OUT-Pad13)") (class "Default")
      (node (ref "U200") (pin "13") (pinfunction "PH1-OSC_OUT_13") (pintype "bidirectional"))
    )
    (net (code "85") (name "unconnected-(U200B-PA0-Pad22)") (class "Default")
      (node (ref "U200") (pin "22") (pinfunction "PA0_22") (pintype "bidirectional"))
    )
    (net (code "86") (name "unconnected-(U200B-PA1-Pad23)") (class "Default")
      (node (ref "U200") (pin "23") (pinfunction "PA1_23") (pintype "bidirectional"))
    )
    (net (code "87") (name "unconnected-(U200B-PA8-Pad67)") (class "Default")
      (node (ref "U200") (pin "67") (pinfunction "PA8_67") (pintype "bidirectional"))
    )
    (net (code "88") (name "unconnected-(U200B-PA9-Pad68)") (class "Default")
      (node (ref "U200") (pin "68") (pinfunction "PA9_68") (pintype "bidirectional"))
    )
    (net (code "89") (name "unconnected-(U200B-PA10-Pad69)") (class "Default")
      (node (ref "U200") (pin "69") (pinfunction "PA10_69") (pintype "bidirectional"))
    )
    (net (code "90") (name "unconnected-(U200B-PB0-Pad34)") (class "Default")
      (node (ref "U200") (pin "34") (pinfunction "PB0_34") (pintype "bidirectional"))
    )
    (net (code "91") (name "unconnected-(U200B-PB1-Pad35)") (class "Default")
      (node (ref "U200") (pin "35") (pinfunction "PB1_35") (pintype "bidirectional"))
    )
    (net (code "92") (name "unconnected-(U200B-PB5-Pad91)") (class "Default")
      (node (ref "U200") (pin "91") (pinfunction "PB5_91") (pintype "bidirectional"))
    )
    (net (code "93") (name "unconnected-(U200B-PC0-Pad15)") (class "Default")
      (node (ref "U200") (pin "15") (pinfunction "PC0_15") (pintype "bidirectional"))
    )
    (net (code "94") (name "unconnected-(U200B-PC1-Pad16)") (class "Default")
      (node (ref "U200") (pin "16") (pinfunction "PC1_16") (pintype "bidirectional"))
    )
    (net (code "95") (name "unconnected-(U200B-PC3_C-Pad18)") (class "Default")
      (node (ref "U200") (pin "18") (pinfunction "PC3_C_18") (pintype "input"))
    )
    (net (code "96") (name "unconnected-(U200B-PC5-Pad33)") (class "Default")
      (node (ref "U200") (pin "33") (pinfunction "PC5_33") (pintype "bidirectional"))
    )
    (net (code "97") (name "unconnected-(U200B-PC6-Pad63)") (class "Default")
      (node (ref "U200") (pin "63") (pinfunction "PC6_63") (pintype "bidirectional"))
    )
    (net (code "98") (name "unconnected-(U200B-PC7-Pad64)") (class "Default")
      (node (ref "U200") (pin "64") (pinfunction "PC7_64") (pintype "bidirectional"))
    )
    (net (code "99") (name "unconnected-(U200B-PC8-Pad65)") (class "Default")
      (node (ref "U200") (pin "65") (pinfunction "PC8_65") (pintype "bidirectional"))
    )
    (net (code "100") (name "unconnected-(U200B-PC9-Pad66)") (class "Default")
      (node (ref "U200") (pin "66") (pinfunction "PC9_66") (pintype "bidirectional"))
    )
    (net (code "101") (name "unconnected-(U200B-PC10-Pad78)") (class "Default")
      (node (ref "U200") (pin "78") (pinfunction "PC10_78") (pintype "bidirectional"))
    )
    (net (code "102") (name "unconnected-(U200B-PC13-Pad7)") (class "Default")
      (node (ref "U200") (pin "7") (pinfunction "PC13_7") (pintype "bidirectional"))
    )
    (net (code "103") (name "unconnected-(U200B-PC14-OSC32_IN-Pad8)") (class "Default")
      (node (ref "U200") (pin "8") (pinfunction "PC14-OSC32_IN_8") (pintype "bidirectional"))
    )
    (net (code "104") (name "unconnected-(U200B-PC15-OSC32_OUT-Pad9)") (class "Default")
      (node (ref "U200") (pin "9") (pinfunction "PC15-OSC32_OUT_9") (pintype "bidirectional"))
    )
    (net (code "105") (name "unconnected-(U200C-PD0-Pad81)") (class "Default")
      (node (ref "U200") (pin "81") (pinfunction "PD0_81") (pintype "bidirectional"))
    )
    (net (code "106") (name "unconnected-(U200C-PD1-Pad82)") (class "Default")
      (node (ref "U200") (pin "82") (pinfunction "PD1_82") (pintype "bidirectional"))
    )
    (net (code "107") (name "unconnected-(U200C-PD2-Pad83)") (class "Default")
      (node (ref "U200") (pin "83") (pinfunction "PD2_83") (pintype "bidirectional"))
    )
    (net (code "108") (name "unconnected-(U200C-PD3-Pad84)") (class "Default")
      (node (ref "U200") (pin "84") (pinfunction "PD3_84") (pintype "bidirectional"))
    )
    (net (code "109") (name "unconnected-(U200C-PD4-Pad85)") (class "Default")
      (node (ref "U200") (pin "85") (pinfunction "PD4_85") (pintype "bidirectional"))
    )
    (net (code "110") (name "unconnected-(U200C-PD5-Pad86)") (class "Default")
      (node (ref "U200") (pin "86") (pinfunction "PD5_86") (pintype "bidirectional"))
    )
    (net (code "111") (name "unconnected-(U200C-PD6-Pad87)") (class "Default")
      (node (ref "U200") (pin "87") (pinfunction "PD6_87") (pintype "bidirectional"))
    )
    (net (code "112") (name "unconnected-(U200C-PD7-Pad88)") (class "Default")
      (node (ref "U200") (pin "88") (pinfunction "PD7_88") (pintype "bidirectional"))
    )
    (net (code "113") (name "unconnected-(U200C-PD8-Pad55)") (class "Default")
      (node (ref "U200") (pin "55") (pinfunction "PD8_55") (pintype "bidirectional"))
    )
    (net (code "114") (name "unconnected-(U200C-PD9-Pad56)") (class "Default")
      (node (ref "U200") (pin "56") (pinfunction "PD9_56") (pintype "bidirectional"))
    )
    (net (code "115") (name "unconnected-(U200C-PD10-Pad57)") (class "Default")
      (node (ref "U200") (pin "57") (pinfunction "PD10_57") (pintype "bidirectional"))
    )
    (net (code "116") (name "unconnected-(U200C-PD11-Pad58)") (class "Default")
      (node (ref "U200") (pin "58") (pinfunction "PD11_58") (pintype "bidirectional"))
    )
    (net (code "117") (name "unconnected-(U200C-PD12-Pad59)") (class "Default")
      (node (ref "U200") (pin "59") (pinfunction "PD12_59") (pintype "bidirectional"))
    )
    (net (code "118") (name "unconnected-(U200C-PD13-Pad60)") (class "Default")
      (node (ref "U200") (pin "60") (pinfunction "PD13_60") (pintype "bidirectional"))
    )
    (net (code "119") (name "unconnected-(U200C-PE11-Pad41)") (class "Default")
      (node (ref "U200") (pin "41") (pinfunction "PE11_41") (pintype "bidirectional"))
    )
    (net (code "120") (name "unconnected-(U200C-PE12-Pad42)") (class "Default")
      (node (ref "U200") (pin "42") (pinfunction "PE12_42") (pintype "bidirectional"))
    )
    (net (code "121") (name "unconnected-(U202A-EP-Pad25)") (class "Default")
      (node (ref "U202") (pin "25") (pinfunction "EP_25") (pintype "passive"))
    )
    (net (code "122") (name "unconnected-(U202A-RESV-Pad19)") (class "Default")
      (node (ref "U202") (pin "19") (pinfunction "RESV_19") (pintype "passive+no_connect"))
    )
  )
)
